# STN1110_RN-42.net
KiCad netlist of a schematic drawn in Altium Designer
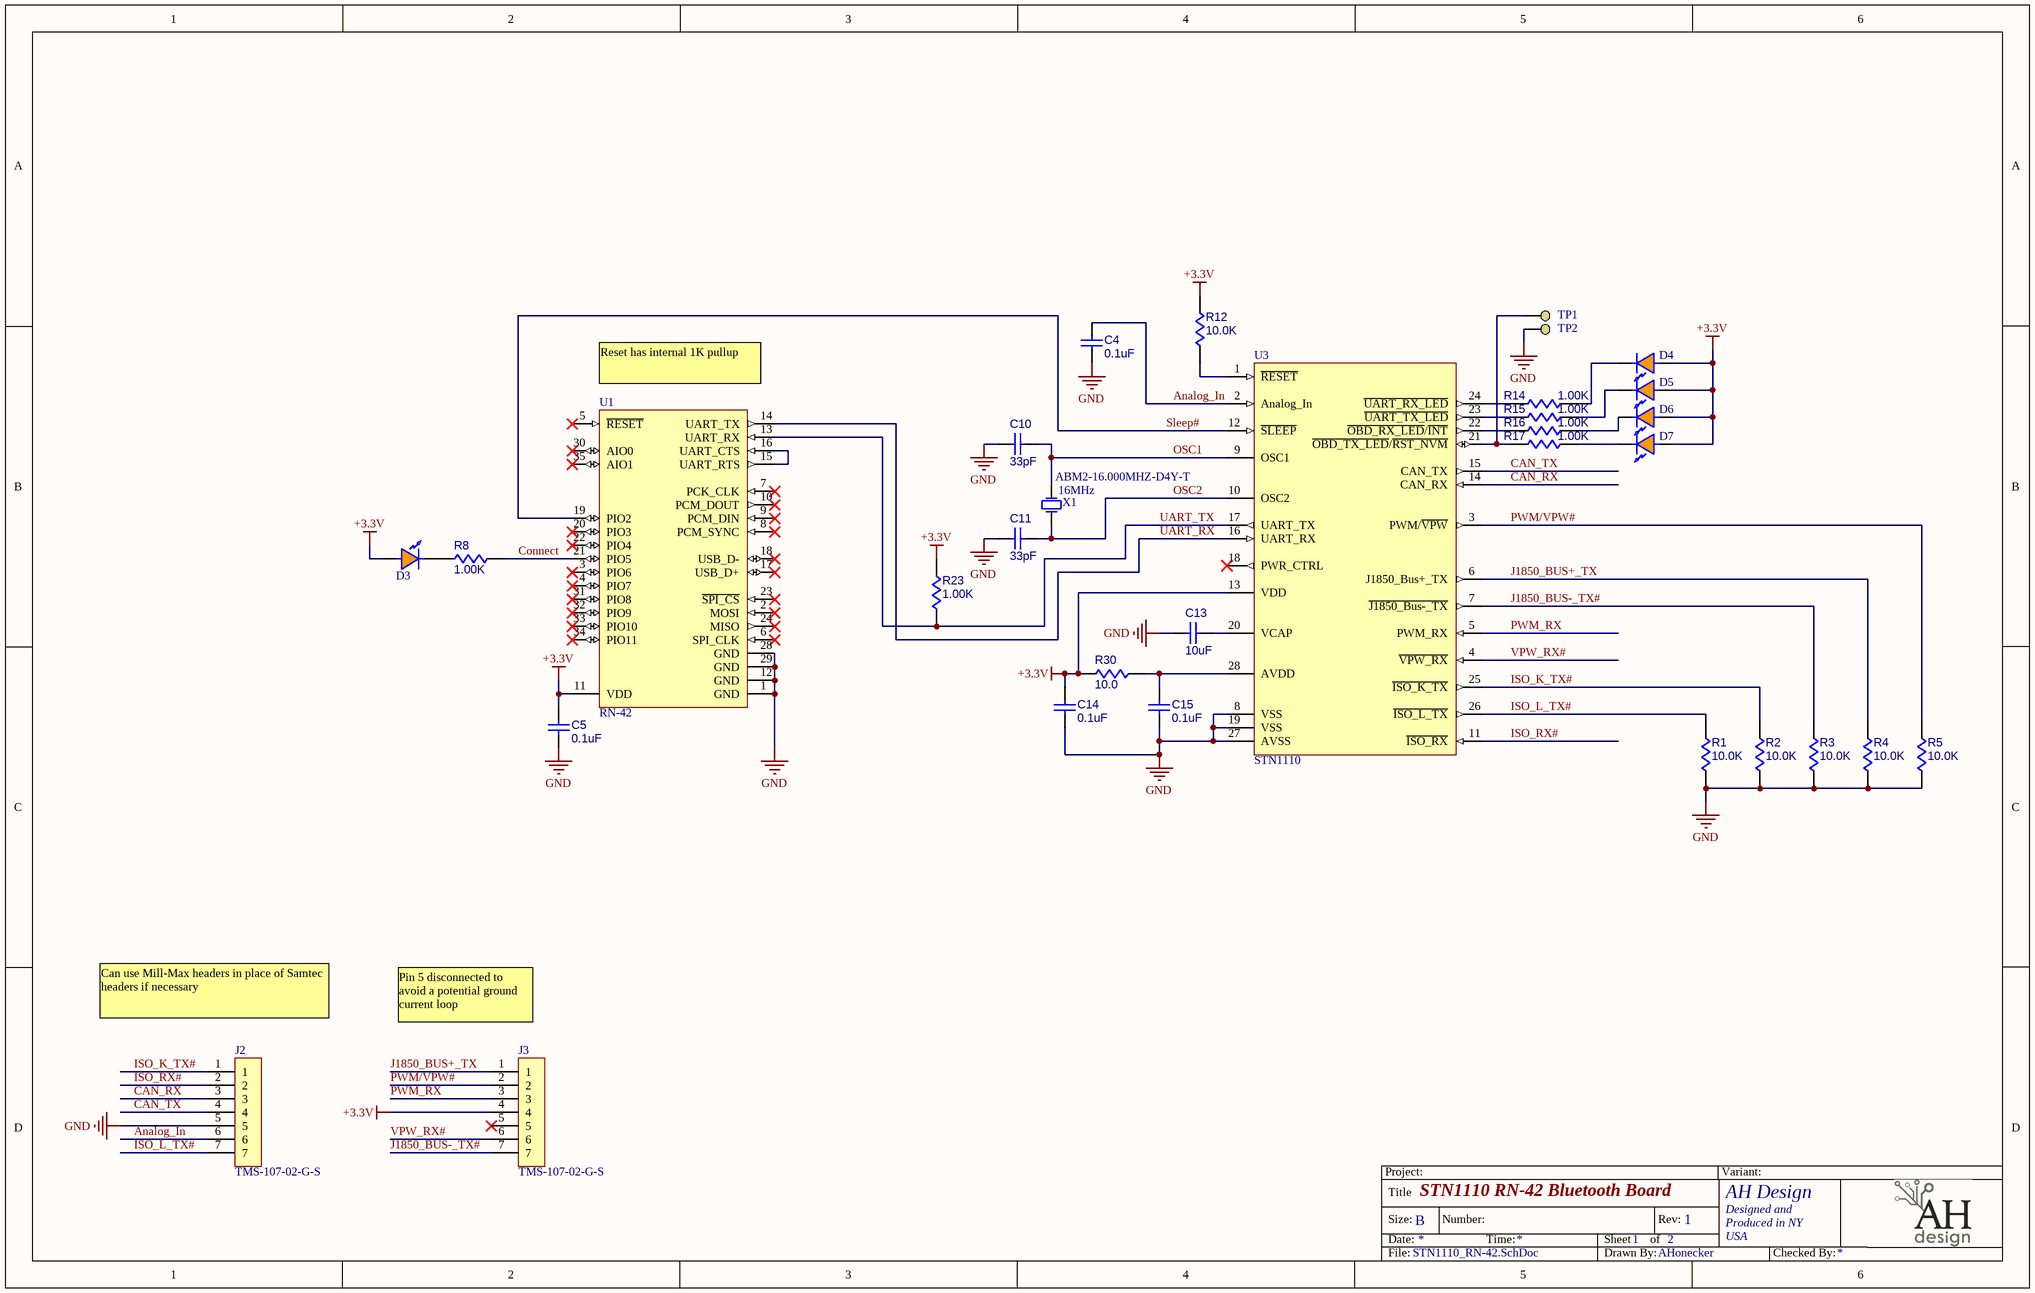
[diagram p0: STN1110_RN-42.SchDoc]

(export (version "E")
  (design (tool "Eeschema 10.0.6"))
  (components
    (comp (ref "C4")
      (value "0.1uF")
      (footprint "CC0603")
      (description "0.1uF 50V, in a CC0603, X7R ,+/-20%,LF")
      (fields
        (field (name "VOLTAGE") "50")
        (field (name "MANUFACTURER") "Kemet")
        (field (name "PUBLISHER") "AltiumdBManager")
        (field (name "APPROVED") "Pending")
      )
      (libsource (lib "VanteonStd") (part "CAP"))
    )
    (comp (ref "C5")
      (value "0.1uF")
      (footprint "CC0603")
      (description "0.1uF 50V, in a CC0603, X7R ,+/-20%,LF")
      (fields
        (field (name "VOLTAGE") "50")
        (field (name "MANUFACTURER") "Kemet")
        (field (name "PUBLISHER") "AltiumdBManager")
        (field (name "APPROVED") "Pending")
      )
      (libsource (lib "VanteonStd") (part "CAP"))
    )
    (comp (ref "C10")
      (value "33pF")
      (footprint "CC0603")
      (description "33pF 16V, in a CC0603, COG ,+/-1%,LF")
      (fields
        (field (name "VOLTAGE") "16")
        (field (name "MANUFACTURER") "Kemet Electronics Corp")
        (field (name "PUBLISHER") "AltiumDBManager1.4-MWyman")
        (field (name "APPROVED") "Yes")
        (field (name "APPROVER") "IHS")
      )
      (libsource (lib "VanteonStd") (part "CAP"))
    )
    (comp (ref "C11")
      (value "33pF")
      (footprint "CC0603")
      (description "33pF 16V, in a CC0603, COG ,+/-1%,LF")
      (fields
        (field (name "VOLTAGE") "16")
        (field (name "MANUFACTURER") "Kemet Electronics Corp")
        (field (name "PUBLISHER") "AltiumDBManager1.4-MWyman")
        (field (name "APPROVED") "Yes")
        (field (name "APPROVER") "IHS")
      )
      (libsource (lib "VanteonStd") (part "CAP"))
    )
    (comp (ref "C13")
      (value "10uF")
      (footprint "CC0805")
      (description "10uF 6.3V, in a CC0805, X5R ,+/-20%,LF")
      (fields
        (field (name "VOLTAGE") "6.3")
        (field (name "MANUFACTURER") "Kemet Electronics Corp")
        (field (name "PUBLISHER") "AltiumDBManager1.4-MWyman")
        (field (name "APPROVED") "Yes")
        (field (name "APPROVER") "IHS")
      )
      (libsource (lib "VanteonStd") (part "CAP"))
    )
    (comp (ref "C14")
      (value "0.1uF")
      (footprint "CC0603")
      (description "0.1uF 50V, in a CC0603, X7R ,+/-20%,LF")
      (fields
        (field (name "VOLTAGE") "50")
        (field (name "MANUFACTURER") "Kemet")
        (field (name "PUBLISHER") "AltiumdBManager")
        (field (name "APPROVED") "Pending")
      )
      (libsource (lib "VanteonStd") (part "CAP"))
    )
    (comp (ref "C15")
      (value "0.1uF")
      (footprint "CC0603")
      (description "0.1uF 50V, in a CC0603, X7R ,+/-20%,LF")
      (fields
        (field (name "VOLTAGE") "50")
        (field (name "MANUFACTURER") "Kemet")
        (field (name "PUBLISHER") "AltiumdBManager")
        (field (name "APPROVED") "Pending")
      )
      (libsource (lib "VanteonStd") (part "CAP"))
    )
    (comp (ref "D3")
      (value "APA1606SECK")
      (footprint "KINGBRIGHT_APA1606SECK")
      (description "LED 1.6X0.6MM 601NM Orange Right-Angle SMD")
      (fields
        (field (name "MANUFACTURER") "Kingbright Corp.")
        (field (name "APPROVED") "No")
        (field (name "PUBLISHER") "Vanteon - AHonecker")
      )
      (libsource (lib "AndyHoneckerNewComp") (part "KINGBRIGHT_APA1606SECK"))
    )
    (comp (ref "D4")
      (value "APA1606SECK")
      (footprint "KINGBRIGHT_APA1606SECK")
      (description "LED 1.6X0.6MM 601NM Orange Right-Angle SMD")
      (fields
        (field (name "MANUFACTURER") "Kingbright Corp.")
        (field (name "APPROVED") "No")
        (field (name "PUBLISHER") "Vanteon - AHonecker")
      )
      (libsource (lib "AndyHoneckerNewComp") (part "KINGBRIGHT_APA1606SECK"))
    )
    (comp (ref "D5")
      (value "APA1606SECK")
      (footprint "KINGBRIGHT_APA1606SECK")
      (description "LED 1.6X0.6MM 601NM Orange Right-Angle SMD")
      (fields
        (field (name "MANUFACTURER") "Kingbright Corp.")
        (field (name "APPROVED") "No")
        (field (name "PUBLISHER") "Vanteon - AHonecker")
      )
      (libsource (lib "AndyHoneckerNewComp") (part "KINGBRIGHT_APA1606SECK"))
    )
    (comp (ref "D6")
      (value "APA1606SECK")
      (footprint "KINGBRIGHT_APA1606SECK")
      (description "LED 1.6X0.6MM 601NM Orange Right-Angle SMD")
      (fields
        (field (name "MANUFACTURER") "Kingbright Corp.")
        (field (name "APPROVED") "No")
        (field (name "PUBLISHER") "Vanteon - AHonecker")
      )
      (libsource (lib "AndyHoneckerNewComp") (part "KINGBRIGHT_APA1606SECK"))
    )
    (comp (ref "D7")
      (value "APA1606SECK")
      (footprint "KINGBRIGHT_APA1606SECK")
      (description "LED 1.6X0.6MM 601NM Orange Right-Angle SMD")
      (fields
        (field (name "MANUFACTURER") "Kingbright Corp.")
        (field (name "APPROVED") "No")
        (field (name "PUBLISHER") "Vanteon - AHonecker")
      )
      (libsource (lib "AndyHoneckerNewComp") (part "KINGBRIGHT_APA1606SECK"))
    )
    (comp (ref "J2")
      (value "TMS-107-02-G-S")
      (footprint "Samtec_TMS-107-02-G-S")
      (description "7 pin through hole micro header, 50mil pitch")
      (fields (field (name "MANUFACTURER") "Samtec"))
      (libsource (lib "Andy_Parts") (part "Samtec_TMS-107-02-G-S"))
    )
    (comp (ref "J3")
      (value "TMS-107-02-G-S")
      (footprint "Samtec_TMS-107-02-G-S")
      (description "7 pin through hole micro header, 50mil pitch")
      (fields (field (name "MANUFACTURER") "Samtec"))
      (libsource (lib "Andy_Parts") (part "Samtec_TMS-107-02-G-S"))
    )
    (comp (ref "R1")
      (value "10.0K")
      (footprint "R0603")
      (description "10.0K, Gen Purp Chip, R0603 0.1W 1%")
      (fields
        (field (name "MANUFACTURER") "Panasonic")
        (field (name "PARTNUMBER") "ERJ3EKF1002V")
        (field (name "PUBLISHER") "AltiumDBManager1.1")
      )
      (libsource (lib "VanteonStd") (part "RES"))
    )
    (comp (ref "R2")
      (value "10.0K")
      (footprint "R0603")
      (description "10.0K, Gen Purp Chip, R0603 0.1W 1%")
      (fields
        (field (name "MANUFACTURER") "Panasonic")
        (field (name "PARTNUMBER") "ERJ3EKF1002V")
        (field (name "PUBLISHER") "AltiumDBManager1.1")
      )
      (libsource (lib "VanteonStd") (part "RES"))
    )
    (comp (ref "R3")
      (value "10.0K")
      (footprint "R0603")
      (description "10.0K, Gen Purp Chip, R0603 0.1W 1%")
      (fields
        (field (name "MANUFACTURER") "Panasonic")
        (field (name "PARTNUMBER") "ERJ3EKF1002V")
        (field (name "PUBLISHER") "AltiumDBManager1.1")
      )
      (libsource (lib "VanteonStd") (part "RES"))
    )
    (comp (ref "R4")
      (value "10.0K")
      (footprint "R0603")
      (description "10.0K, Gen Purp Chip, R0603 0.1W 1%")
      (fields
        (field (name "MANUFACTURER") "Panasonic")
        (field (name "PARTNUMBER") "ERJ3EKF1002V")
        (field (name "PUBLISHER") "AltiumDBManager1.1")
      )
      (libsource (lib "VanteonStd") (part "RES"))
    )
    (comp (ref "R5")
      (value "10.0K")
      (footprint "R0603")
      (description "10.0K, Gen Purp Chip, R0603 0.1W 1%")
      (fields
        (field (name "MANUFACTURER") "Panasonic")
        (field (name "PARTNUMBER") "ERJ3EKF1002V")
        (field (name "PUBLISHER") "AltiumDBManager1.1")
      )
      (libsource (lib "VanteonStd") (part "RES"))
    )
    (comp (ref "R8")
      (value "1.00K")
      (footprint "R0603")
      (description "1.00K, Gen Purp Chip, R0603 0.1W 1%")
      (fields
        (field (name "MANUFACTURER") "Panasonic")
        (field (name "PARTNUMBER") "ERJ3EKF1001V")
        (field (name "PUBLISHER") "AltiumDBManager1.1")
      )
      (libsource (lib "VanteonStd") (part "RES"))
    )
    (comp (ref "R12")
      (value "10.0K")
      (footprint "R0603")
      (description "10.0K, Gen Purp Chip, R0603 0.1W 1%")
      (fields
        (field (name "MANUFACTURER") "Panasonic")
        (field (name "PARTNUMBER") "ERJ3EKF1002V")
        (field (name "PUBLISHER") "AltiumDBManager1.1")
      )
      (libsource (lib "VanteonStd") (part "RES"))
    )
    (comp (ref "R14")
      (value "1.00K")
      (footprint "R0603")
      (description "1.00K, Gen Purp Chip, R0603 0.1W 1%")
      (fields
        (field (name "MANUFACTURER") "Panasonic")
        (field (name "PARTNUMBER") "RK73H1JTTD1001F")
        (field (name "PUBLISHER") "AltiumDBManager1.4-MWyman")
        (field (name "APPROVED") "Yes")
        (field (name "APPROVER") "IHS")
      )
      (libsource (lib "VanteonStd") (part "RES"))
    )
    (comp (ref "R15")
      (value "1.00K")
      (footprint "R0603")
      (description "1.00K, Gen Purp Chip, R0603 0.1W 1%")
      (fields
        (field (name "MANUFACTURER") "Panasonic")
        (field (name "PARTNUMBER") "RK73H1JTTD1001F")
        (field (name "PUBLISHER") "AltiumDBManager1.4-MWyman")
        (field (name "APPROVED") "Yes")
        (field (name "APPROVER") "IHS")
      )
      (libsource (lib "VanteonStd") (part "RES"))
    )
    (comp (ref "R16")
      (value "1.00K")
      (footprint "R0603")
      (description "1.00K, Gen Purp Chip, R0603 0.1W 1%")
      (fields
        (field (name "MANUFACTURER") "Panasonic")
        (field (name "PARTNUMBER") "RK73H1JTTD1001F")
        (field (name "PUBLISHER") "AltiumDBManager1.4-MWyman")
        (field (name "APPROVED") "Yes")
        (field (name "APPROVER") "IHS")
      )
      (libsource (lib "VanteonStd") (part "RES"))
    )
    (comp (ref "R17")
      (value "1.00K")
      (footprint "R0603")
      (description "1.00K, Gen Purp Chip, R0603 0.1W 1%")
      (fields
        (field (name "MANUFACTURER") "Panasonic")
        (field (name "PARTNUMBER") "RK73H1JTTD1001F")
        (field (name "PUBLISHER") "AltiumDBManager1.4-MWyman")
        (field (name "APPROVED") "Yes")
        (field (name "APPROVER") "IHS")
      )
      (libsource (lib "VanteonStd") (part "RES"))
    )
    (comp (ref "R23")
      (value "1.00K")
      (footprint "R0603")
      (description "1.00K, Gen Purp Chip, R0603 0.1W 1%")
      (fields
        (field (name "MANUFACTURER") "Panasonic")
        (field (name "PARTNUMBER") "ERJ3EKF1001V")
        (field (name "PUBLISHER") "AltiumDBManager1.1")
      )
      (libsource (lib "VanteonStd") (part "RES"))
    )
    (comp (ref "R30")
      (value "10.0")
      (footprint "R0603")
      (description "10.0, Gen Purp Chip, R0603 0.1W 1%")
      (fields
        (field (name "MANUFACTURER") "Panasonic")
        (field (name "PARTNUMBER") "ERJ3EKF10R0V")
        (field (name "PUBLISHER") "AltiumDBManager1.1")
      )
      (libsource (lib "VanteonStd") (part "RES"))
    )
    (comp (ref "TP1")
      (value "~")
      (footprint "TP,0.5mmx0.5mm,RND")
      (description "0.5mm diameter testpoint")
      (libsource (lib "STN1110_RN-42") (part "TP, 0.5mm x 0.5mm SMT, RND"))
    )
    (comp (ref "TP2")
      (value "~")
      (footprint "TP,0.5mmx0.5mm,RND")
      (description "0.5mm diameter testpoint")
      (libsource (lib "STN1110_RN-42") (part "TP, 0.5mm x 0.5mm SMT, RND"))
    )
    (comp (ref "U1")
      (value "RN-42")
      (footprint "RN-42")
      (description "Roving Networks Bluetooth Serial Module")
      (fields (field (name "MANUFACTURER") "Roving Networks"))
      (libsource (lib "Andy_Parts") (part "RN-42"))
    )
    (comp (ref "U3")
      (value "STN1110")
      (footprint "SOIC127P1030X264-28N")
      (description "ELM327 Improved Replacement; Multiprotocol OBDII Scanner")
      (fields (field (name "MANUFACTURER") "ScanTool.net"))
      (libsource (lib "Andy_Parts") (part "STN1110_SOIC"))
    )
    (comp (ref "X1")
      (value "ABM2-16.000MHZ-D4Y-T")
      (footprint "Abracon_ABM2_Series")
      (description "CRYSTAL 16.00 MHZ 18PF SMD")
      (fields (field (name "MANUFACTURER") "Abracon") (field (name "ALTIUM_VALUE") "16MHz"))
      (libsource (lib "Andy_Parts") (part "ABM2-16.000MHZ-D4Y-T"))
    )
  )
  (nets
    (net (code "1") (name "+3.3V") (class "Default")
      (node (ref "C14") (pin "1") (pinfunction "1_1") (pintype "passive"))
      (node (ref "C5") (pin "1") (pinfunction "1_1") (pintype "passive"))
      (node (ref "D3") (pin "A") (pinfunction "A_A") (pintype "passive"))
      (node (ref "D4") (pin "A") (pinfunction "A_A") (pintype "passive"))
      (node (ref "D5") (pin "A") (pinfunction "A_A") (pintype "passive"))
      (node (ref "D6") (pin "A") (pinfunction "A_A") (pintype "passive"))
      (node (ref "D7") (pin "A") (pinfunction "A_A") (pintype "passive"))
      (node (ref "J3") (pin "4") (pinfunction "4_4") (pintype "passive"))
      (node (ref "R12") (pin "2") (pinfunction "2_2") (pintype "passive"))
      (node (ref "R23") (pin "2") (pinfunction "2_2") (pintype "passive"))
      (node (ref "R30") (pin "1") (pinfunction "1_1") (pintype "passive"))
      (node (ref "U1") (pin "11") (pinfunction "VDD_11") (pintype "power_in"))
      (node (ref "U3") (pin "13") (pinfunction "VDD_13") (pintype "power_in"))
    )
    (net (code "2") (name "/Analog_In") (class "Default")
      (node (ref "C4") (pin "2") (pinfunction "2_2") (pintype "passive"))
      (node (ref "J2") (pin "6") (pinfunction "6_6") (pintype "passive"))
      (node (ref "U3") (pin "2") (pinfunction "Analog_In_2") (pintype "input"))
    )
    (net (code "3") (name "/CAN_RX") (class "Default")
      (node (ref "J2") (pin "3") (pinfunction "3_3") (pintype "passive"))
      (node (ref "U3") (pin "14") (pinfunction "CAN_RX_14") (pintype "input"))
    )
    (net (code "4") (name "/CAN_TX") (class "Default")
      (node (ref "J2") (pin "4") (pinfunction "4_4") (pintype "passive"))
      (node (ref "U3") (pin "15") (pinfunction "CAN_TX_15") (pintype "output"))
    )
    (net (code "5") (name "/Connect") (class "Default")
      (node (ref "R8") (pin "1") (pinfunction "1_1") (pintype "passive"))
      (node (ref "U1") (pin "21") (pinfunction "PIO5_21") (pintype "bidirectional"))
    )
    (net (code "6") (name "/ISO_K_TX#") (class "Default")
      (node (ref "J2") (pin "1") (pinfunction "1_1") (pintype "passive"))
      (node (ref "R2") (pin "1") (pinfunction "1_1") (pintype "passive"))
      (node (ref "U3") (pin "25") (pinfunction "~{ISO_K_TX}_25") (pintype "output"))
    )
    (net (code "7") (name "/ISO_L_TX#") (class "Default")
      (node (ref "J2") (pin "7") (pinfunction "7_7") (pintype "passive"))
      (node (ref "R1") (pin "1") (pinfunction "1_1") (pintype "passive"))
      (node (ref "U3") (pin "26") (pinfunction "~{ISO_L_TX}_26") (pintype "output"))
    )
    (net (code "8") (name "/ISO_RX#") (class "Default")
      (node (ref "J2") (pin "2") (pinfunction "2_2") (pintype "passive"))
      (node (ref "U3") (pin "11") (pinfunction "~{ISO_RX}_11") (pintype "input"))
    )
    (net (code "9") (name "/J1850_BUS+_TX") (class "Default")
      (node (ref "J3") (pin "1") (pinfunction "1_1") (pintype "passive"))
      (node (ref "R4") (pin "1") (pinfunction "1_1") (pintype "passive"))
      (node (ref "U3") (pin "6") (pinfunction "J1850_Bus+_TX_6") (pintype "output"))
    )
    (net (code "10") (name "/J1850_BUS-_TX#") (class "Default")
      (node (ref "J3") (pin "7") (pinfunction "7_7") (pintype "passive"))
      (node (ref "R3") (pin "1") (pinfunction "1_1") (pintype "passive"))
      (node (ref "U3") (pin "7") (pinfunction "~{J1850_Bus-_TX}_7") (pintype "output"))
    )
    (net (code "11") (name "/OSC1") (class "Default")
      (node (ref "C10") (pin "2") (pinfunction "2_2") (pintype "passive"))
      (node (ref "U3") (pin "9") (pinfunction "OSC1_9") (pintype "passive"))
      (node (ref "X1") (pin "2") (pinfunction "OSC2_2") (pintype "passive"))
    )
    (net (code "12") (name "/OSC2") (class "Default")
      (node (ref "C11") (pin "2") (pinfunction "2_2") (pintype "passive"))
      (node (ref "U3") (pin "10") (pinfunction "OSC2_10") (pintype "passive"))
      (node (ref "X1") (pin "1") (pinfunction "OSC1_1") (pintype "passive"))
    )
    (net (code "13") (name "/PWM_RX") (class "Default")
      (node (ref "J3") (pin "3") (pinfunction "3_3") (pintype "passive"))
      (node (ref "U3") (pin "5") (pinfunction "PWM_RX_5") (pintype "input"))
    )
    (net (code "14") (name "/PWM{slash}VPW#") (class "Default")
      (node (ref "J3") (pin "2") (pinfunction "2_2") (pintype "passive"))
      (node (ref "R5") (pin "1") (pinfunction "1_1") (pintype "passive"))
      (node (ref "U3") (pin "3") (pinfunction "PWM/~{VPW}_3") (pintype "output"))
    )
    (net (code "15") (name "/Sleep#") (class "Default")
      (node (ref "U1") (pin "19") (pinfunction "PIO2_19") (pintype "bidirectional"))
      (node (ref "U3") (pin "12") (pinfunction "~{SLEEP}_12") (pintype "input"))
    )
    (net (code "16") (name "/UART_RX") (class "Default")
      (node (ref "U1") (pin "14") (pinfunction "UART_TX_14") (pintype "output"))
      (node (ref "U3") (pin "16") (pinfunction "UART_RX_16") (pintype "input"))
    )
    (net (code "17") (name "/UART_TX") (class "Default")
      (node (ref "R23") (pin "1") (pinfunction "1_1") (pintype "passive"))
      (node (ref "U1") (pin "13") (pinfunction "UART_RX_13") (pintype "input"))
      (node (ref "U3") (pin "17") (pinfunction "UART_TX_17") (pintype "output"))
    )
    (net (code "18") (name "/VPW_RX#") (class "Default")
      (node (ref "J3") (pin "6") (pinfunction "6_6") (pintype "passive"))
      (node (ref "U3") (pin "4") (pinfunction "~{VPW_RX}_4") (pintype "input"))
    )
    (net (code "19") (name "GND") (class "Default")
      (node (ref "C10") (pin "1") (pinfunction "1_1") (pintype "passive"))
      (node (ref "C11") (pin "1") (pinfunction "1_1") (pintype "passive"))
      (node (ref "C13") (pin "2") (pinfunction "2_2") (pintype "passive"))
      (node (ref "C14") (pin "2") (pinfunction "2_2") (pintype "passive"))
      (node (ref "C15") (pin "2") (pinfunction "2_2") (pintype "passive"))
      (node (ref "C4") (pin "1") (pinfunction "1_1") (pintype "passive"))
      (node (ref "C5") (pin "2") (pinfunction "2_2") (pintype "passive"))
      (node (ref "J2") (pin "5") (pinfunction "5_5") (pintype "passive"))
      (node (ref "R1") (pin "2") (pinfunction "2_2") (pintype "passive"))
      (node (ref "R2") (pin "2") (pinfunction "2_2") (pintype "passive"))
      (node (ref "R3") (pin "2") (pinfunction "2_2") (pintype "passive"))
      (node (ref "R4") (pin "2") (pinfunction "2_2") (pintype "passive"))
      (node (ref "R5") (pin "2") (pinfunction "2_2") (pintype "passive"))
      (node (ref "TP2") (pin "1") (pinfunction "TP_1") (pintype "passive"))
      (node (ref "U1") (pin "1") (pinfunction "GND_1") (pintype "power_in"))
      (node (ref "U1") (pin "12") (pinfunction "GND_12") (pintype "power_in"))
      (node (ref "U1") (pin "28") (pinfunction "GND_28") (pintype "power_in"))
      (node (ref "U1") (pin "29") (pinfunction "GND_29") (pintype "power_in"))
      (node (ref "U3") (pin "19") (pinfunction "VSS_19") (pintype "power_in"))
      (node (ref "U3") (pin "27") (pinfunction "AVSS_27") (pintype "power_in"))
      (node (ref "U3") (pin "8") (pinfunction "VSS_8") (pintype "power_in"))
    )
    (net (code "20") (name "Net-(D3-PadC)") (class "Default")
      (node (ref "D3") (pin "C") (pinfunction "C_C") (pintype "passive"))
      (node (ref "R8") (pin "2") (pinfunction "2_2") (pintype "passive"))
    )
    (net (code "21") (name "Net-(D4-PadC)") (class "Default")
      (node (ref "D4") (pin "C") (pinfunction "C_C") (pintype "passive"))
      (node (ref "R14") (pin "1") (pinfunction "1_1") (pintype "passive"))
    )
    (net (code "22") (name "Net-(D5-PadC)") (class "Default")
      (node (ref "D5") (pin "C") (pinfunction "C_C") (pintype "passive"))
      (node (ref "R15") (pin "1") (pinfunction "1_1") (pintype "passive"))
    )
    (net (code "23") (name "Net-(D6-PadC)") (class "Default")
      (node (ref "D6") (pin "C") (pinfunction "C_C") (pintype "passive"))
      (node (ref "R16") (pin "1") (pinfunction "1_1") (pintype "passive"))
    )
    (net (code "24") (name "Net-(D7-PadC)") (class "Default")
      (node (ref "D7") (pin "C") (pinfunction "C_C") (pintype "passive"))
      (node (ref "R17") (pin "1") (pinfunction "1_1") (pintype "passive"))
    )
    (net (code "25") (name "Net-(TP1-TP)") (class "Default")
      (node (ref "R17") (pin "2") (pinfunction "2_2") (pintype "passive"))
      (node (ref "TP1") (pin "1") (pinfunction "TP_1") (pintype "passive"))
      (node (ref "U3") (pin "21") (pinfunction "~{OBD_TX_LED}/~{RST_NVM}_21") (pintype "bidirectional"))
    )
    (net (code "26") (name "Net-(U1-UART_CTS)") (class "Default")
      (node (ref "U1") (pin "15") (pinfunction "UART_RTS_15") (pintype "output"))
      (node (ref "U1") (pin "16") (pinfunction "UART_CTS_16") (pintype "input"))
    )
    (net (code "27") (name "Net-(U3-AVDD)") (class "Default")
      (node (ref "C15") (pin "1") (pinfunction "1_1") (pintype "passive"))
      (node (ref "R30") (pin "2") (pinfunction "2_2") (pintype "passive"))
      (node (ref "U3") (pin "28") (pinfunction "AVDD_28") (pintype "power_in"))
    )
    (net (code "28") (name "Net-(U3-VCAP)") (class "Default")
      (node (ref "C13") (pin "1") (pinfunction "1_1") (pintype "passive"))
      (node (ref "U3") (pin "20") (pinfunction "VCAP_20") (pintype "power_in"))
    )
    (net (code "29") (name "Net-(U3-~{OBD_RX_LED}{slash}~{INT})") (class "Default")
      (node (ref "R16") (pin "2") (pinfunction "2_2") (pintype "passive"))
      (node (ref "U3") (pin "22") (pinfunction "~{OBD_RX_LED}/~{INT}_22") (pintype "output"))
    )
    (net (code "30") (name "Net-(U3-~{RESET})") (class "Default")
      (node (ref "R12") (pin "1") (pinfunction "1_1") (pintype "passive"))
      (node (ref "U3") (pin "1") (pinfunction "~{RESET}_1") (pintype "input"))
    )
    (net (code "31") (name "Net-(U3-~{UART_RX_LED})") (class "Default")
      (node (ref "R14") (pin "2") (pinfunction "2_2") (pintype "passive"))
      (node (ref "U3") (pin "24") (pinfunction "~{UART_RX_LED}_24") (pintype "output"))
    )
    (net (code "32") (name "Net-(U3-~{UART_TX_LED})") (class "Default")
      (node (ref "R15") (pin "2") (pinfunction "2_2") (pintype "passive"))
      (node (ref "U3") (pin "23") (pinfunction "~{UART_TX_LED}_23") (pintype "output"))
    )
    (net (code "33") (name "unconnected-(J3-Pad5)") (class "Default")
      (node (ref "J3") (pin "5") (pinfunction "5_5") (pintype "passive+no_connect"))
    )
    (net (code "34") (name "unconnected-(U1-AIO0-Pad30)") (class "Default")
      (node (ref "U1") (pin "30") (pinfunction "AIO0_30") (pintype "bidirectional+no_connect"))
    )
    (net (code "35") (name "unconnected-(U1-AIO1-Pad35)") (class "Default")
      (node (ref "U1") (pin "35") (pinfunction "AIO1_35") (pintype "bidirectional+no_connect"))
    )
    (net (code "36") (name "unconnected-(U1-MISO-Pad24)") (class "Default")
      (node (ref "U1") (pin "24") (pinfunction "MISO_24") (pintype "output+no_connect"))
    )
    (net (code "37") (name "unconnected-(U1-MOSI-Pad2)") (class "Default")
      (node (ref "U1") (pin "2") (pinfunction "MOSI_2") (pintype "input+no_connect"))
    )
    (net (code "38") (name "unconnected-(U1-PCK_CLK-Pad7)") (class "Default")
      (node (ref "U1") (pin "7") (pinfunction "PCK_CLK_7") (pintype "input+no_connect"))
    )
    (net (code "39") (name "unconnected-(U1-PCM_DIN-Pad9)") (class "Default")
      (node (ref "U1") (pin "9") (pinfunction "PCM_DIN_9") (pintype "input+no_connect"))
    )
    (net (code "40") (name "unconnected-(U1-PCM_DOUT-Pad10)") (class "Default")
      (node (ref "U1") (pin "10") (pinfunction "PCM_DOUT_10") (pintype "output+no_connect"))
    )
    (net (code "41") (name "unconnected-(U1-PCM_SYNC-Pad8)") (class "Default")
      (node (ref "U1") (pin "8") (pinfunction "PCM_SYNC_8") (pintype "input+no_connect"))
    )
    (net (code "42") (name "unconnected-(U1-PIO3-Pad20)") (class "Default")
      (node (ref "U1") (pin "20") (pinfunction "PIO3_20") (pintype "bidirectional+no_connect"))
    )
    (net (code "43") (name "unconnected-(U1-PIO4-Pad22)") (class "Default")
      (node (ref "U1") (pin "22") (pinfunction "PIO4_22") (pintype "bidirectional+no_connect"))
    )
    (net (code "44") (name "unconnected-(U1-PIO6-Pad3)") (class "Default")
      (node (ref "U1") (pin "3") (pinfunction "PIO6_3") (pintype "bidirectional+no_connect"))
    )
    (net (code "45") (name "unconnected-(U1-PIO7-Pad4)") (class "Default")
      (node (ref "U1") (pin "4") (pinfunction "PIO7_4") (pintype "bidirectional+no_connect"))
    )
    (net (code "46") (name "unconnected-(U1-PIO8-Pad31)") (class "Default")
      (node (ref "U1") (pin "31") (pinfunction "PIO8_31") (pintype "bidirectional+no_connect"))
    )
    (net (code "47") (name "unconnected-(U1-PIO9-Pad32)") (class "Default")
      (node (ref "U1") (pin "32") (pinfunction "PIO9_32") (pintype "bidirectional+no_connect"))
    )
    (net (code "48") (name "unconnected-(U1-PIO10-Pad33)") (class "Default")
      (node (ref "U1") (pin "33") (pinfunction "PIO10_33") (pintype "bidirectional+no_connect"))
    )
    (net (code "49") (name "unconnected-(U1-PIO11-Pad34)") (class "Default")
      (node (ref "U1") (pin "34") (pinfunction "PIO11_34") (pintype "bidirectional+no_connect"))
    )
    (net (code "50") (name "unconnected-(U1-SPI_CLK-Pad6)") (class "Default")
      (node (ref "U1") (pin "6") (pinfunction "SPI_CLK_6") (pintype "input+no_connect"))
    )
    (net (code "51") (name "unconnected-(U1-USB_D+-Pad17)") (class "Default")
      (node (ref "U1") (pin "17") (pinfunction "USB_D+_17") (pintype "bidirectional+no_connect"))
    )
    (net (code "52") (name "unconnected-(U1-USB_D--Pad18)") (class "Default")
      (node (ref "U1") (pin "18") (pinfunction "USB_D-_18") (pintype "bidirectional+no_connect"))
    )
    (net (code "53") (name "unconnected-(U1-~{RESET}-Pad5)") (class "Default")
      (node (ref "U1") (pin "5") (pinfunction "~{RESET}_5") (pintype "input+no_connect"))
    )
    (net (code "54") (name "unconnected-(U1-~{SPI_CS}-Pad23)") (class "Default")
      (node (ref "U1") (pin "23") (pinfunction "~{SPI_CS}_23") (pintype "input+no_connect"))
    )
    (net (code "55") (name "unconnected-(U3-PWR_CTRL-Pad18)") (class "Default")
      (node (ref "U3") (pin "18") (pinfunction "PWR_CTRL_18") (pintype "output+no_connect"))
    )
  )
)
